# open-bldc.net
KiCad netlist of a schematic drawn in EAGLE
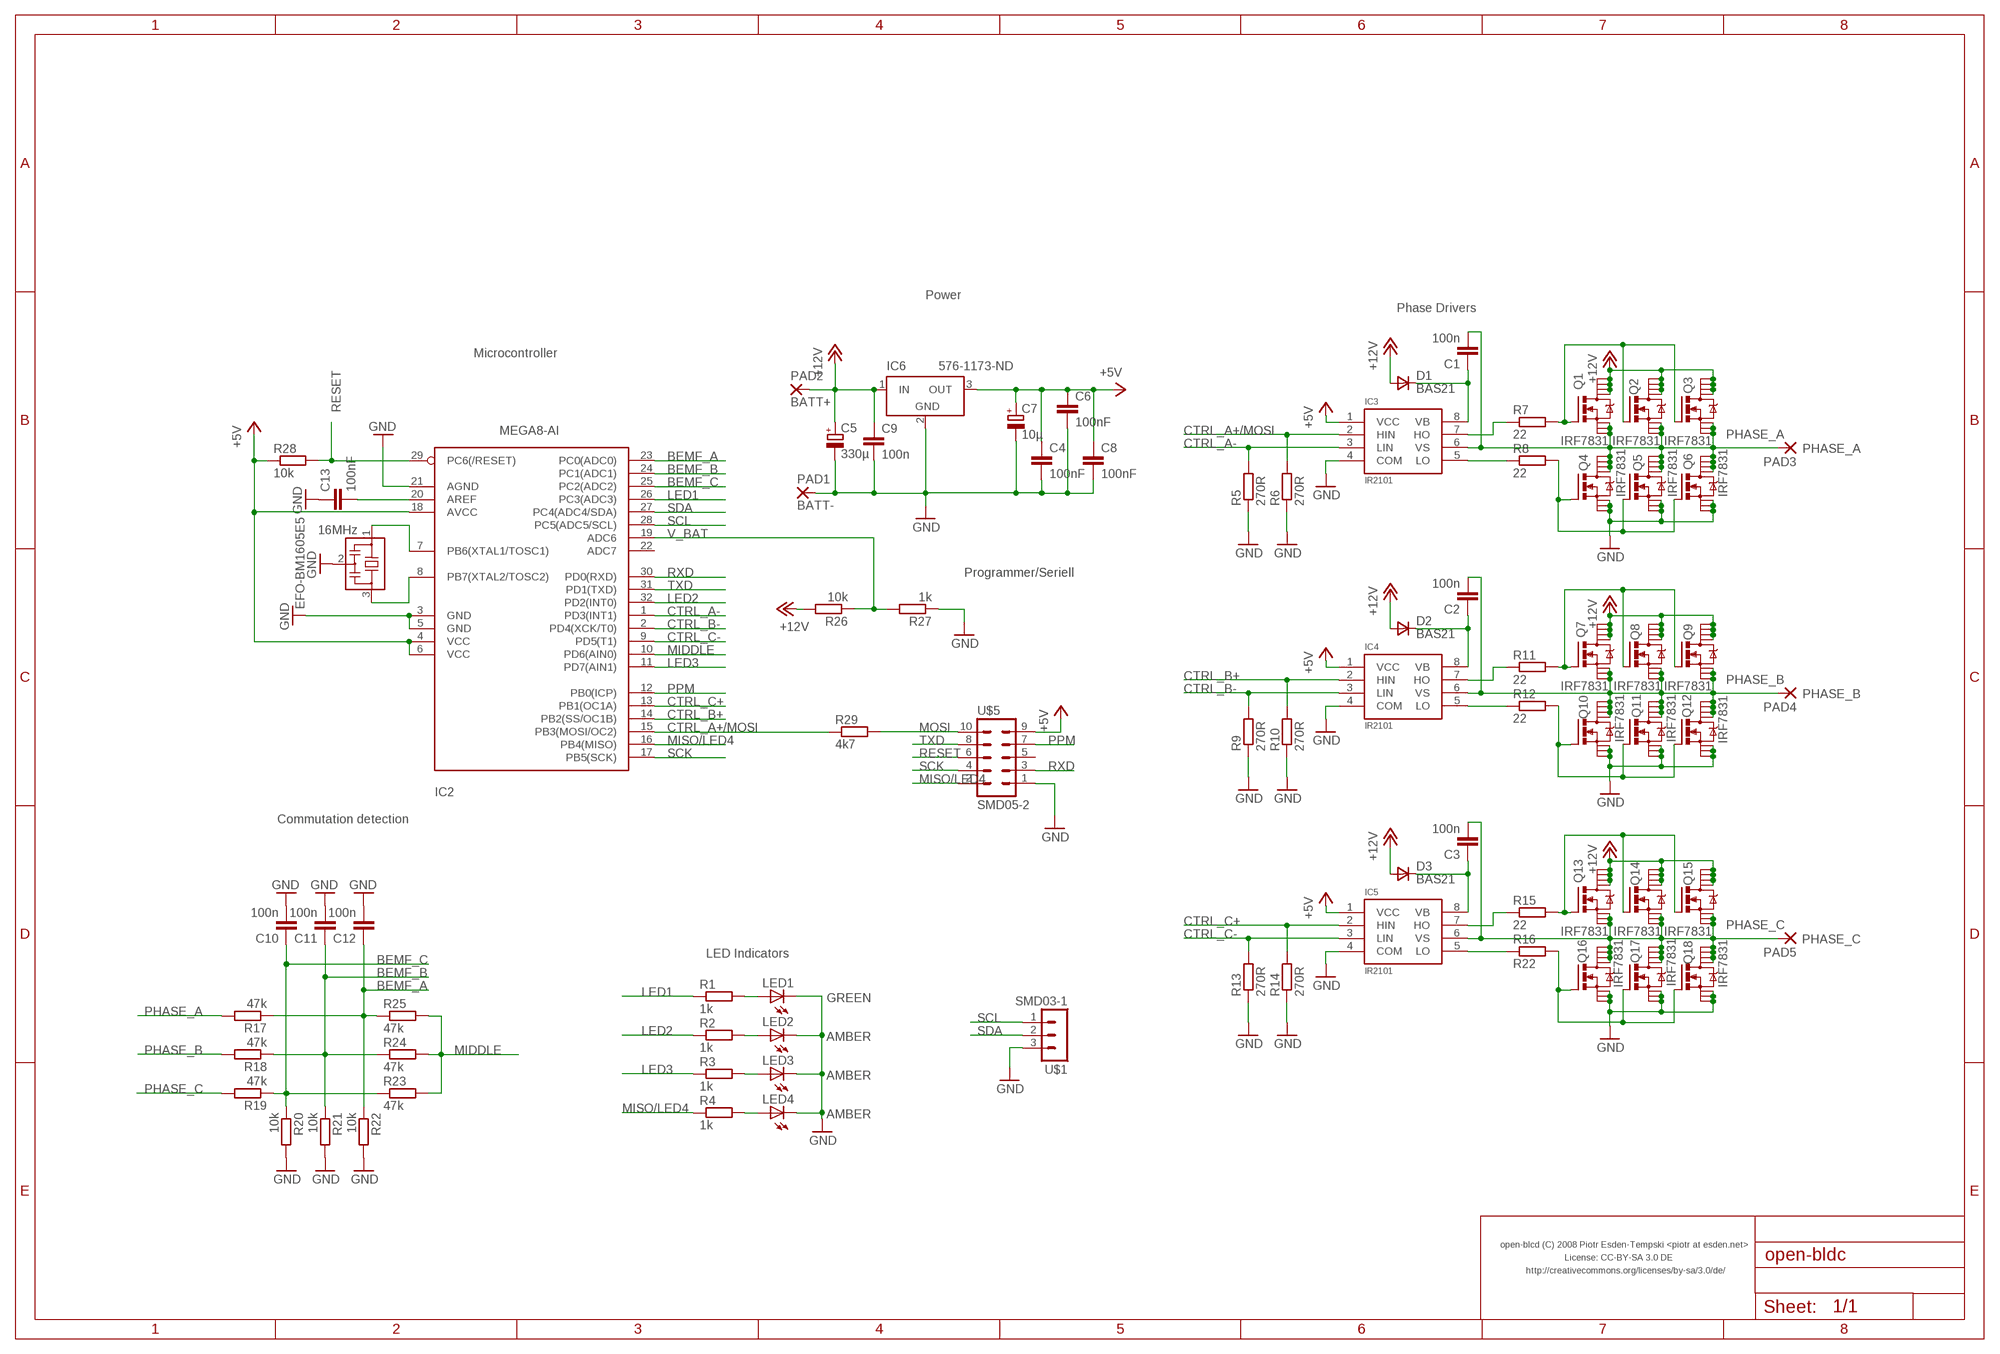
[diagram p0: schematic, sheet 1]

(export (version "E")
  (design (tool "Eeschema 10.0.6"))
  (components
    (comp (ref "C1")
      (value "100n")
      (footprint "eagle-import:C0603")
      (libsource (lib "eagle-import") (part "C-EUC0603"))
    )
    (comp (ref "C2")
      (value "100n")
      (footprint "eagle-import:C0603")
      (libsource (lib "eagle-import") (part "C-EUC0603"))
    )
    (comp (ref "C3")
      (value "100n")
      (footprint "eagle-import:C0603")
      (libsource (lib "eagle-import") (part "C-EUC0603"))
    )
    (comp (ref "C4")
      (value "100nF")
      (footprint "eagle-import:C0603")
      (libsource (lib "eagle-import") (part "C-EUC0603"))
    )
    (comp (ref "C5")
      (value "330µ")
      (footprint "eagle-import:E3,5-8")
      (libsource (lib "eagle-import") (part "CPOL-EUE3.5-8"))
    )
    (comp (ref "C6")
      (value "100nF")
      (footprint "eagle-import:C0603")
      (libsource (lib "eagle-import") (part "C-EUC0603"))
    )
    (comp (ref "C7")
      (value "10µ")
      (footprint "eagle-import:D_7343-31R")
      (libsource (lib "eagle-import") (part "CPOL-EUD/7343-31R"))
    )
    (comp (ref "C8")
      (value "100nF")
      (footprint "eagle-import:C0603")
      (libsource (lib "eagle-import") (part "C-EUC0603"))
    )
    (comp (ref "C9")
      (value "100n")
      (footprint "eagle-import:C0603")
      (libsource (lib "eagle-import") (part "C-EUC0603"))
    )
    (comp (ref "C10")
      (value "100n")
      (footprint "eagle-import:C0603")
      (libsource (lib "eagle-import") (part "C-EUC0603"))
    )
    (comp (ref "C11")
      (value "100n")
      (footprint "eagle-import:C0603")
      (libsource (lib "eagle-import") (part "C-EUC0603"))
    )
    (comp (ref "C12")
      (value "100n")
      (footprint "eagle-import:C0603")
      (libsource (lib "eagle-import") (part "C-EUC0603"))
    )
    (comp (ref "C13")
      (value "100nF")
      (footprint "eagle-import:C0603")
      (libsource (lib "eagle-import") (part "C-EUC0603"))
    )
    (comp (ref "D1")
      (value "BAS21")
      (footprint "eagle-import:SOT-23")
      (libsource (lib "eagle-import") (part "VAR2SOT23"))
    )
    (comp (ref "D2")
      (value "BAS21")
      (footprint "eagle-import:SOT-23")
      (libsource (lib "eagle-import") (part "VAR2SOT23"))
    )
    (comp (ref "D3")
      (value "BAS21")
      (footprint "eagle-import:SOT-23")
      (libsource (lib "eagle-import") (part "VAR2SOT23"))
    )
    (comp (ref "EFO-BM1605E5")
      (value "16MHz")
      (footprint "eagle-import:EFOBM")
      (libsource (lib "eagle-import") (part "EFOBM"))
    )
    (comp (ref "IC2")
      (value "MEGA8-AI")
      (footprint "eagle-import:TQFP32-08")
      (libsource (lib "eagle-import") (part "MEGA8-AI"))
    )
    (comp (ref "IC3")
      (value "IR2101")
      (footprint "eagle-import:SO-8")
      (libsource (lib "eagle-import") (part "IR2101"))
    )
    (comp (ref "IC4")
      (value "IR2101")
      (footprint "eagle-import:SO-8")
      (libsource (lib "eagle-import") (part "IR2101"))
    )
    (comp (ref "IC5")
      (value "IR2101")
      (footprint "eagle-import:SO-8")
      (libsource (lib "eagle-import") (part "IR2101"))
    )
    (comp (ref "IC6")
      (value "576-1173-ND")
      (footprint "eagle-import:SOT223")
      (libsource (lib "eagle-import") (part "LT1129CST5"))
    )
    (comp (ref "LED1")
      (value "GREEN")
      (footprint "eagle-import:CHIP-LED0603")
      (libsource (lib "eagle-import") (part "LEDCHIP-LED0603"))
    )
    (comp (ref "LED2")
      (value "AMBER")
      (footprint "eagle-import:CHIP-LED0603")
      (libsource (lib "eagle-import") (part "LEDCHIP-LED0603"))
    )
    (comp (ref "LED3")
      (value "AMBER")
      (footprint "eagle-import:CHIP-LED0603")
      (libsource (lib "eagle-import") (part "LEDCHIP-LED0603"))
    )
    (comp (ref "LED4")
      (value "AMBER")
      (footprint "eagle-import:CHIP-LED0603")
      (libsource (lib "eagle-import") (part "LEDCHIP-LED0603"))
    )
    (comp (ref "PAD1")
      (value "BATT-")
      (footprint "eagle-import:SMD2,54-5,08")
      (libsource (lib "eagle-import") (part "SMD5"))
    )
    (comp (ref "PAD2")
      (value "BATT+")
      (footprint "eagle-import:SMD2,54-5,08")
      (libsource (lib "eagle-import") (part "SMD5"))
    )
    (comp (ref "PAD3")
      (value "PHASE_A")
      (footprint "eagle-import:SMD2,54-5,08")
      (libsource (lib "eagle-import") (part "SMD5"))
    )
    (comp (ref "PAD4")
      (value "PHASE_B")
      (footprint "eagle-import:SMD2,54-5,08")
      (libsource (lib "eagle-import") (part "SMD5"))
    )
    (comp (ref "PAD5")
      (value "PHASE_C")
      (footprint "eagle-import:SMD2,54-5,08")
      (libsource (lib "eagle-import") (part "SMD5"))
    )
    (comp (ref "Q1")
      (value "IRF7831")
      (footprint "eagle-import:SO-08")
      (libsource (lib "eagle-import") (part "N-MOSFET-SO8S"))
    )
    (comp (ref "Q2")
      (value "IRF7831")
      (footprint "eagle-import:SO-08")
      (libsource (lib "eagle-import") (part "N-MOSFET-SO8S"))
    )
    (comp (ref "Q3")
      (value "IRF7831")
      (footprint "eagle-import:SO-08")
      (libsource (lib "eagle-import") (part "N-MOSFET-SO8S"))
    )
    (comp (ref "Q4")
      (value "IRF7831")
      (footprint "eagle-import:SO-08")
      (libsource (lib "eagle-import") (part "N-MOSFET-SO8S"))
    )
    (comp (ref "Q5")
      (value "IRF7831")
      (footprint "eagle-import:SO-08")
      (libsource (lib "eagle-import") (part "N-MOSFET-SO8S"))
    )
    (comp (ref "Q6")
      (value "IRF7831")
      (footprint "eagle-import:SO-08")
      (libsource (lib "eagle-import") (part "N-MOSFET-SO8S"))
    )
    (comp (ref "Q7")
      (value "IRF7831")
      (footprint "eagle-import:SO-08")
      (libsource (lib "eagle-import") (part "N-MOSFET-SO8S"))
    )
    (comp (ref "Q8")
      (value "IRF7831")
      (footprint "eagle-import:SO-08")
      (libsource (lib "eagle-import") (part "N-MOSFET-SO8S"))
    )
    (comp (ref "Q9")
      (value "IRF7831")
      (footprint "eagle-import:SO-08")
      (libsource (lib "eagle-import") (part "N-MOSFET-SO8S"))
    )
    (comp (ref "Q10")
      (value "IRF7831")
      (footprint "eagle-import:SO-08")
      (libsource (lib "eagle-import") (part "N-MOSFET-SO8S"))
    )
    (comp (ref "Q11")
      (value "IRF7831")
      (footprint "eagle-import:SO-08")
      (libsource (lib "eagle-import") (part "N-MOSFET-SO8S"))
    )
    (comp (ref "Q12")
      (value "IRF7831")
      (footprint "eagle-import:SO-08")
      (libsource (lib "eagle-import") (part "N-MOSFET-SO8S"))
    )
    (comp (ref "Q13")
      (value "IRF7831")
      (footprint "eagle-import:SO-08")
      (libsource (lib "eagle-import") (part "N-MOSFET-SO8S"))
    )
    (comp (ref "Q14")
      (value "IRF7831")
      (footprint "eagle-import:SO-08")
      (libsource (lib "eagle-import") (part "N-MOSFET-SO8S"))
    )
    (comp (ref "Q15")
      (value "IRF7831")
      (footprint "eagle-import:SO-08")
      (libsource (lib "eagle-import") (part "N-MOSFET-SO8S"))
    )
    (comp (ref "Q16")
      (value "IRF7831")
      (footprint "eagle-import:SO-08")
      (libsource (lib "eagle-import") (part "N-MOSFET-SO8S"))
    )
    (comp (ref "Q17")
      (value "IRF7831")
      (footprint "eagle-import:SO-08")
      (libsource (lib "eagle-import") (part "N-MOSFET-SO8S"))
    )
    (comp (ref "Q18")
      (value "IRF7831")
      (footprint "eagle-import:SO-08")
      (libsource (lib "eagle-import") (part "N-MOSFET-SO8S"))
    )
    (comp (ref "R1")
      (value "1k")
      (footprint "eagle-import:R0603")
      (libsource (lib "eagle-import") (part "R-EU_R0603"))
    )
    (comp (ref "R2")
      (value "1k")
      (footprint "eagle-import:R0603")
      (libsource (lib "eagle-import") (part "R-EU_R0603"))
    )
    (comp (ref "R3")
      (value "1k")
      (footprint "eagle-import:R0603")
      (libsource (lib "eagle-import") (part "R-EU_R0603"))
    )
    (comp (ref "R4")
      (value "1k")
      (footprint "eagle-import:R0603")
      (libsource (lib "eagle-import") (part "R-EU_R0603"))
    )
    (comp (ref "R5")
      (value "270R")
      (footprint "eagle-import:R0603")
      (libsource (lib "eagle-import") (part "R-EU_R0603"))
    )
    (comp (ref "R6")
      (value "270R")
      (footprint "eagle-import:R0603")
      (libsource (lib "eagle-import") (part "R-EU_R0603"))
    )
    (comp (ref "R7")
      (value "22")
      (footprint "eagle-import:R0603")
      (libsource (lib "eagle-import") (part "R-EU_R0603"))
    )
    (comp (ref "R8")
      (value "22")
      (footprint "eagle-import:R0603")
      (libsource (lib "eagle-import") (part "R-EU_R0603"))
    )
    (comp (ref "R9")
      (value "270R")
      (footprint "eagle-import:R0603")
      (libsource (lib "eagle-import") (part "R-EU_R0603"))
    )
    (comp (ref "R10")
      (value "270R")
      (footprint "eagle-import:R0603")
      (libsource (lib "eagle-import") (part "R-EU_R0603"))
    )
    (comp (ref "R11")
      (value "22")
      (footprint "eagle-import:R0603")
      (libsource (lib "eagle-import") (part "R-EU_R0603"))
    )
    (comp (ref "R12")
      (value "22")
      (footprint "eagle-import:R0603")
      (libsource (lib "eagle-import") (part "R-EU_R0603"))
    )
    (comp (ref "R13")
      (value "270R")
      (footprint "eagle-import:R0603")
      (libsource (lib "eagle-import") (part "R-EU_R0603"))
    )
    (comp (ref "R14")
      (value "270R")
      (footprint "eagle-import:R0603")
      (libsource (lib "eagle-import") (part "R-EU_R0603"))
    )
    (comp (ref "R15")
      (value "22")
      (footprint "eagle-import:R0603")
      (libsource (lib "eagle-import") (part "R-EU_R0603"))
    )
    (comp (ref "R16")
      (value "R22")
      (footprint "eagle-import:R0603")
      (libsource (lib "eagle-import") (part "R-EU_R0603"))
    )
    (comp (ref "R17")
      (value "47k")
      (footprint "eagle-import:R0603")
      (libsource (lib "eagle-import") (part "R-EU_R0603"))
    )
    (comp (ref "R18")
      (value "47k")
      (footprint "eagle-import:R0603")
      (libsource (lib "eagle-import") (part "R-EU_R0603"))
    )
    (comp (ref "R19")
      (value "47k")
      (footprint "eagle-import:R0603")
      (libsource (lib "eagle-import") (part "R-EU_R0603"))
    )
    (comp (ref "R20")
      (value "10k")
      (footprint "eagle-import:R0603")
      (libsource (lib "eagle-import") (part "R-EU_R0603"))
    )
    (comp (ref "R21")
      (value "10k")
      (footprint "eagle-import:R0603")
      (libsource (lib "eagle-import") (part "R-EU_R0603"))
    )
    (comp (ref "R22")
      (value "10k")
      (footprint "eagle-import:R0603")
      (libsource (lib "eagle-import") (part "R-EU_R0603"))
    )
    (comp (ref "R23")
      (value "47k")
      (footprint "eagle-import:R0603")
      (libsource (lib "eagle-import") (part "R-EU_R0603"))
    )
    (comp (ref "R24")
      (value "47k")
      (footprint "eagle-import:R0603")
      (libsource (lib "eagle-import") (part "R-EU_R0603"))
    )
    (comp (ref "R25")
      (value "47k")
      (footprint "eagle-import:R0603")
      (libsource (lib "eagle-import") (part "R-EU_R0603"))
    )
    (comp (ref "R26")
      (value "10k")
      (footprint "eagle-import:R0603")
      (libsource (lib "eagle-import") (part "R-EU_R0603"))
    )
    (comp (ref "R27")
      (value "1k")
      (footprint "eagle-import:R0603")
      (libsource (lib "eagle-import") (part "R-EU_R0603"))
    )
    (comp (ref "R28")
      (value "10k")
      (footprint "eagle-import:R0603")
      (libsource (lib "eagle-import") (part "R-EU_R0603"))
    )
    (comp (ref "R29")
      (value "4k7")
      (footprint "eagle-import:R0603")
      (libsource (lib "eagle-import") (part "R-EU_R0603"))
    )
    (comp (ref "U$1")
      (value "SMD03-1")
      (footprint "eagle-import:SMD03-1")
      (libsource (lib "eagle-import") (part "SMD03-1"))
    )
    (comp (ref "U$5")
      (value "SMD05-2")
      (footprint "eagle-import:SMD05-2")
      (libsource (lib "eagle-import") (part "SMD05-2"))
    )
  )
  (nets
    (net (code "1") (name "+5V") (class "Default")
      (node (ref "C4") (pin "1") (pinfunction "1_1") (pintype "passive"))
      (node (ref "C6") (pin "1") (pinfunction "1_1") (pintype "passive"))
      (node (ref "C7") (pin "+") (pinfunction "+_+") (pintype "passive"))
      (node (ref "C8") (pin "1") (pinfunction "1_1") (pintype "passive"))
      (node (ref "IC2") (pin "18") (pinfunction "AVCC_18") (pintype "power_in"))
      (node (ref "IC2") (pin "4") (pinfunction "VCC_4") (pintype "power_in"))
      (node (ref "IC2") (pin "6") (pinfunction "VCC_6") (pintype "power_in"))
      (node (ref "IC3") (pin "1") (pinfunction "VCC_1") (pintype "bidirectional"))
      (node (ref "IC4") (pin "1") (pinfunction "VCC_1") (pintype "bidirectional"))
      (node (ref "IC5") (pin "1") (pinfunction "VCC_1") (pintype "bidirectional"))
      (node (ref "IC6") (pin "3") (pinfunction "OUT_3") (pintype "output"))
      (node (ref "R28") (pin "1") (pinfunction "1_1") (pintype "passive"))
      (node (ref "U$5") (pin "9") (pinfunction "9_9") (pintype "passive"))
    )
    (net (code "2") (name "+12V") (class "Default")
      (node (ref "C5") (pin "+") (pinfunction "+_+") (pintype "passive"))
      (node (ref "C9") (pin "1") (pinfunction "1_1") (pintype "passive"))
      (node (ref "D1") (pin "3") (pinfunction "A_3") (pintype "passive"))
      (node (ref "D2") (pin "3") (pinfunction "A_3") (pintype "passive"))
      (node (ref "D3") (pin "3") (pinfunction "A_3") (pintype "passive"))
      (node (ref "IC6") (pin "1") (pinfunction "IN_1") (pintype "input"))
      (node (ref "PAD2") (pin "1") (pinfunction "P_1") (pintype "passive"))
      (node (ref "Q1") (pin "5") (pinfunction "D_5") (pintype "passive"))
      (node (ref "Q1") (pin "6") (pinfunction "D_6") (pintype "passive"))
      (node (ref "Q1") (pin "7") (pinfunction "D_7") (pintype "passive"))
      (node (ref "Q1") (pin "8") (pinfunction "D_8") (pintype "passive"))
      (node (ref "Q13") (pin "5") (pinfunction "D_5") (pintype "passive"))
      (node (ref "Q13") (pin "6") (pinfunction "D_6") (pintype "passive"))
      (node (ref "Q13") (pin "7") (pinfunction "D_7") (pintype "passive"))
      (node (ref "Q13") (pin "8") (pinfunction "D_8") (pintype "passive"))
      (node (ref "Q14") (pin "5") (pinfunction "D_5") (pintype "passive"))
      (node (ref "Q14") (pin "6") (pinfunction "D_6") (pintype "passive"))
      (node (ref "Q14") (pin "7") (pinfunction "D_7") (pintype "passive"))
      (node (ref "Q14") (pin "8") (pinfunction "D_8") (pintype "passive"))
      (node (ref "Q15") (pin "5") (pinfunction "D_5") (pintype "passive"))
      (node (ref "Q15") (pin "6") (pinfunction "D_6") (pintype "passive"))
      (node (ref "Q15") (pin "7") (pinfunction "D_7") (pintype "passive"))
      (node (ref "Q15") (pin "8") (pinfunction "D_8") (pintype "passive"))
      (node (ref "Q2") (pin "5") (pinfunction "D_5") (pintype "passive"))
      (node (ref "Q2") (pin "6") (pinfunction "D_6") (pintype "passive"))
      (node (ref "Q2") (pin "7") (pinfunction "D_7") (pintype "passive"))
      (node (ref "Q2") (pin "8") (pinfunction "D_8") (pintype "passive"))
      (node (ref "Q3") (pin "5") (pinfunction "D_5") (pintype "passive"))
      (node (ref "Q3") (pin "6") (pinfunction "D_6") (pintype "passive"))
      (node (ref "Q3") (pin "7") (pinfunction "D_7") (pintype "passive"))
      (node (ref "Q3") (pin "8") (pinfunction "D_8") (pintype "passive"))
      (node (ref "Q7") (pin "5") (pinfunction "D_5") (pintype "passive"))
      (node (ref "Q7") (pin "6") (pinfunction "D_6") (pintype "passive"))
      (node (ref "Q7") (pin "7") (pinfunction "D_7") (pintype "passive"))
      (node (ref "Q7") (pin "8") (pinfunction "D_8") (pintype "passive"))
      (node (ref "Q8") (pin "5") (pinfunction "D_5") (pintype "passive"))
      (node (ref "Q8") (pin "6") (pinfunction "D_6") (pintype "passive"))
      (node (ref "Q8") (pin "7") (pinfunction "D_7") (pintype "passive"))
      (node (ref "Q8") (pin "8") (pinfunction "D_8") (pintype "passive"))
      (node (ref "Q9") (pin "5") (pinfunction "D_5") (pintype "passive"))
      (node (ref "Q9") (pin "6") (pinfunction "D_6") (pintype "passive"))
      (node (ref "Q9") (pin "7") (pinfunction "D_7") (pintype "passive"))
      (node (ref "Q9") (pin "8") (pinfunction "D_8") (pintype "passive"))
      (node (ref "R26") (pin "2") (pinfunction "2_2") (pintype "passive"))
    )
    (net (code "3") (name "/BEMF_A") (class "Default")
      (node (ref "C12") (pin "1") (pinfunction "1_1") (pintype "passive"))
      (node (ref "IC2") (pin "23") (pinfunction "PC0(ADC0)_23") (pintype "bidirectional"))
      (node (ref "R17") (pin "1") (pinfunction "1_1") (pintype "passive"))
      (node (ref "R22") (pin "1") (pinfunction "1_1") (pintype "passive"))
      (node (ref "R25") (pin "1") (pinfunction "1_1") (pintype "passive"))
    )
    (net (code "4") (name "/BEMF_B") (class "Default")
      (node (ref "C11") (pin "1") (pinfunction "1_1") (pintype "passive"))
      (node (ref "IC2") (pin "24") (pinfunction "PC1(ADC1)_24") (pintype "bidirectional"))
      (node (ref "R18") (pin "1") (pinfunction "1_1") (pintype "passive"))
      (node (ref "R21") (pin "1") (pinfunction "1_1") (pintype "passive"))
      (node (ref "R24") (pin "1") (pinfunction "1_1") (pintype "passive"))
    )
    (net (code "5") (name "/BEMF_C") (class "Default")
      (node (ref "C10") (pin "1") (pinfunction "1_1") (pintype "passive"))
      (node (ref "IC2") (pin "25") (pinfunction "PC2(ADC2)_25") (pintype "bidirectional"))
      (node (ref "R19") (pin "1") (pinfunction "1_1") (pintype "passive"))
      (node (ref "R20") (pin "1") (pinfunction "1_1") (pintype "passive"))
      (node (ref "R23") (pin "1") (pinfunction "1_1") (pintype "passive"))
    )
    (net (code "6") (name "/CTRL_A+{slash}MOSI") (class "Default")
      (node (ref "IC2") (pin "15") (pinfunction "PB3(MOSI/OC2)_15") (pintype "bidirectional"))
      (node (ref "IC3") (pin "2") (pinfunction "HIN_2") (pintype "bidirectional"))
      (node (ref "R29") (pin "1") (pinfunction "1_1") (pintype "passive"))
      (node (ref "R6") (pin "2") (pinfunction "2_2") (pintype "passive"))
    )
    (net (code "7") (name "/CTRL_A-") (class "Default")
      (node (ref "IC2") (pin "1") (pinfunction "PD3(INT1)_1") (pintype "bidirectional"))
      (node (ref "IC3") (pin "3") (pinfunction "LIN_3") (pintype "bidirectional"))
      (node (ref "R5") (pin "2") (pinfunction "2_2") (pintype "passive"))
    )
    (net (code "8") (name "/CTRL_B+") (class "Default")
      (node (ref "IC2") (pin "14") (pinfunction "PB2(SS/OC1B)_14") (pintype "bidirectional"))
      (node (ref "IC4") (pin "2") (pinfunction "HIN_2") (pintype "bidirectional"))
      (node (ref "R10") (pin "2") (pinfunction "2_2") (pintype "passive"))
    )
    (net (code "9") (name "/CTRL_B-") (class "Default")
      (node (ref "IC2") (pin "2") (pinfunction "PD4(XCK/T0)_2") (pintype "bidirectional"))
      (node (ref "IC4") (pin "3") (pinfunction "LIN_3") (pintype "bidirectional"))
      (node (ref "R9") (pin "2") (pinfunction "2_2") (pintype "passive"))
    )
    (net (code "10") (name "/CTRL_C+") (class "Default")
      (node (ref "IC2") (pin "13") (pinfunction "PB1(OC1A)_13") (pintype "bidirectional"))
      (node (ref "IC5") (pin "2") (pinfunction "HIN_2") (pintype "bidirectional"))
      (node (ref "R14") (pin "2") (pinfunction "2_2") (pintype "passive"))
    )
    (net (code "11") (name "/CTRL_C-") (class "Default")
      (node (ref "IC2") (pin "9") (pinfunction "PD5(T1)_9") (pintype "bidirectional"))
      (node (ref "IC5") (pin "3") (pinfunction "LIN_3") (pintype "bidirectional"))
      (node (ref "R13") (pin "2") (pinfunction "2_2") (pintype "passive"))
    )
    (net (code "12") (name "/LED1") (class "Default")
      (node (ref "IC2") (pin "26") (pinfunction "PC3(ADC3)_26") (pintype "bidirectional"))
      (node (ref "R1") (pin "1") (pinfunction "1_1") (pintype "passive"))
    )
    (net (code "13") (name "/LED2") (class "Default")
      (node (ref "IC2") (pin "32") (pinfunction "PD2(INT0)_32") (pintype "bidirectional"))
      (node (ref "R2") (pin "1") (pinfunction "1_1") (pintype "passive"))
    )
    (net (code "14") (name "/LED3") (class "Default")
      (node (ref "IC2") (pin "11") (pinfunction "PD7(AIN1)_11") (pintype "bidirectional"))
      (node (ref "R3") (pin "1") (pinfunction "1_1") (pintype "passive"))
    )
    (net (code "15") (name "/MIDDLE") (class "Default")
      (node (ref "IC2") (pin "10") (pinfunction "PD6(AIN0)_10") (pintype "bidirectional"))
      (node (ref "R23") (pin "2") (pinfunction "2_2") (pintype "passive"))
      (node (ref "R24") (pin "2") (pinfunction "2_2") (pintype "passive"))
      (node (ref "R25") (pin "2") (pinfunction "2_2") (pintype "passive"))
    )
    (net (code "16") (name "/MISO{slash}LED4") (class "Default")
      (node (ref "IC2") (pin "16") (pinfunction "PB4(MISO)_16") (pintype "bidirectional"))
      (node (ref "R4") (pin "1") (pinfunction "1_1") (pintype "passive"))
      (node (ref "U$5") (pin "2") (pinfunction "2_2") (pintype "passive"))
    )
    (net (code "17") (name "/MOSI") (class "Default")
      (node (ref "R29") (pin "2") (pinfunction "2_2") (pintype "passive"))
      (node (ref "U$5") (pin "10") (pinfunction "10_10") (pintype "passive"))
    )
    (net (code "18") (name "/PHASE_A") (class "Default")
      (node (ref "C1") (pin "2") (pinfunction "2_2") (pintype "passive"))
      (node (ref "IC3") (pin "6") (pinfunction "VS_6") (pintype "bidirectional"))
      (node (ref "PAD3") (pin "1") (pinfunction "P_1") (pintype "passive"))
      (node (ref "Q1") (pin "1") (pinfunction "S_1") (pintype "passive"))
      (node (ref "Q1") (pin "2") (pinfunction "S_2") (pintype "passive"))
      (node (ref "Q1") (pin "3") (pinfunction "S_3") (pintype "passive"))
      (node (ref "Q2") (pin "1") (pinfunction "S_1") (pintype "passive"))
      (node (ref "Q2") (pin "2") (pinfunction "S_2") (pintype "passive"))
      (node (ref "Q2") (pin "3") (pinfunction "S_3") (pintype "passive"))
      (node (ref "Q3") (pin "1") (pinfunction "S_1") (pintype "passive"))
      (node (ref "Q3") (pin "2") (pinfunction "S_2") (pintype "passive"))
      (node (ref "Q3") (pin "3") (pinfunction "S_3") (pintype "passive"))
      (node (ref "Q4") (pin "5") (pinfunction "D_5") (pintype "passive"))
      (node (ref "Q4") (pin "6") (pinfunction "D_6") (pintype "passive"))
      (node (ref "Q4") (pin "7") (pinfunction "D_7") (pintype "passive"))
      (node (ref "Q4") (pin "8") (pinfunction "D_8") (pintype "passive"))
      (node (ref "Q5") (pin "5") (pinfunction "D_5") (pintype "passive"))
      (node (ref "Q5") (pin "6") (pinfunction "D_6") (pintype "passive"))
      (node (ref "Q5") (pin "7") (pinfunction "D_7") (pintype "passive"))
      (node (ref "Q5") (pin "8") (pinfunction "D_8") (pintype "passive"))
      (node (ref "Q6") (pin "5") (pinfunction "D_5") (pintype "passive"))
      (node (ref "Q6") (pin "6") (pinfunction "D_6") (pintype "passive"))
      (node (ref "Q6") (pin "7") (pinfunction "D_7") (pintype "passive"))
      (node (ref "Q6") (pin "8") (pinfunction "D_8") (pintype "passive"))
      (node (ref "R17") (pin "2") (pinfunction "2_2") (pintype "passive"))
    )
    (net (code "19") (name "/PHASE_B") (class "Default")
      (node (ref "C2") (pin "2") (pinfunction "2_2") (pintype "passive"))
      (node (ref "IC4") (pin "6") (pinfunction "VS_6") (pintype "bidirectional"))
      (node (ref "PAD4") (pin "1") (pinfunction "P_1") (pintype "passive"))
      (node (ref "Q10") (pin "5") (pinfunction "D_5") (pintype "passive"))
      (node (ref "Q10") (pin "6") (pinfunction "D_6") (pintype "passive"))
      (node (ref "Q10") (pin "7") (pinfunction "D_7") (pintype "passive"))
      (node (ref "Q10") (pin "8") (pinfunction "D_8") (pintype "passive"))
      (node (ref "Q11") (pin "5") (pinfunction "D_5") (pintype "passive"))
      (node (ref "Q11") (pin "6") (pinfunction "D_6") (pintype "passive"))
      (node (ref "Q11") (pin "7") (pinfunction "D_7") (pintype "passive"))
      (node (ref "Q11") (pin "8") (pinfunction "D_8") (pintype "passive"))
      (node (ref "Q12") (pin "5") (pinfunction "D_5") (pintype "passive"))
      (node (ref "Q12") (pin "6") (pinfunction "D_6") (pintype "passive"))
      (node (ref "Q12") (pin "7") (pinfunction "D_7") (pintype "passive"))
      (node (ref "Q12") (pin "8") (pinfunction "D_8") (pintype "passive"))
      (node (ref "Q7") (pin "1") (pinfunction "S_1") (pintype "passive"))
      (node (ref "Q7") (pin "2") (pinfunction "S_2") (pintype "passive"))
      (node (ref "Q7") (pin "3") (pinfunction "S_3") (pintype "passive"))
      (node (ref "Q8") (pin "1") (pinfunction "S_1") (pintype "passive"))
      (node (ref "Q8") (pin "2") (pinfunction "S_2") (pintype "passive"))
      (node (ref "Q8") (pin "3") (pinfunction "S_3") (pintype "passive"))
      (node (ref "Q9") (pin "1") (pinfunction "S_1") (pintype "passive"))
      (node (ref "Q9") (pin "2") (pinfunction "S_2") (pintype "passive"))
      (node (ref "Q9") (pin "3") (pinfunction "S_3") (pintype "passive"))
      (node (ref "R18") (pin "2") (pinfunction "2_2") (pintype "passive"))
    )
    (net (code "20") (name "/PHASE_C") (class "Default")
      (node (ref "C3") (pin "2") (pinfunction "2_2") (pintype "passive"))
      (node (ref "IC5") (pin "6") (pinfunction "VS_6") (pintype "bidirectional"))
      (node (ref "PAD5") (pin "1") (pinfunction "P_1") (pintype "passive"))
      (node (ref "Q13") (pin "1") (pinfunction "S_1") (pintype "passive"))
      (node (ref "Q13") (pin "2") (pinfunction "S_2") (pintype "passive"))
      (node (ref "Q13") (pin "3") (pinfunction "S_3") (pintype "passive"))
      (node (ref "Q14") (pin "1") (pinfunction "S_1") (pintype "passive"))
      (node (ref "Q14") (pin "2") (pinfunction "S_2") (pintype "passive"))
      (node (ref "Q14") (pin "3") (pinfunction "S_3") (pintype "passive"))
      (node (ref "Q15") (pin "1") (pinfunction "S_1") (pintype "passive"))
      (node (ref "Q15") (pin "2") (pinfunction "S_2") (pintype "passive"))
      (node (ref "Q15") (pin "3") (pinfunction "S_3") (pintype "passive"))
      (node (ref "Q16") (pin "5") (pinfunction "D_5") (pintype "passive"))
      (node (ref "Q16") (pin "6") (pinfunction "D_6") (pintype "passive"))
      (node (ref "Q16") (pin "7") (pinfunction "D_7") (pintype "passive"))
      (node (ref "Q16") (pin "8") (pinfunction "D_8") (pintype "passive"))
      (node (ref "Q17") (pin "5") (pinfunction "D_5") (pintype "passive"))
      (node (ref "Q17") (pin "6") (pinfunction "D_6") (pintype "passive"))
      (node (ref "Q17") (pin "7") (pinfunction "D_7") (pintype "passive"))
      (node (ref "Q17") (pin "8") (pinfunction "D_8") (pintype "passive"))
      (node (ref "Q18") (pin "5") (pinfunction "D_5") (pintype "passive"))
      (node (ref "Q18") (pin "6") (pinfunction "D_6") (pintype "passive"))
      (node (ref "Q18") (pin "7") (pinfunction "D_7") (pintype "passive"))
      (node (ref "Q18") (pin "8") (pinfunction "D_8") (pintype "passive"))
      (node (ref "R19") (pin "2") (pinfunction "2_2") (pintype "passive"))
    )
    (net (code "21") (name "/PPM") (class "Default")
      (node (ref "IC2") (pin "12") (pinfunction "PB0(ICP)_12") (pintype "bidirectional"))
      (node (ref "U$5") (pin "7") (pinfunction "7_7") (pintype "passive"))
    )
    (net (code "22") (name "/RESET") (class "Default")
      (node (ref "IC2") (pin "29") (pinfunction "PC6(/RESET)_29") (pintype "bidirectional"))
      (node (ref "R28") (pin "2") (pinfunction "2_2") (pintype "passive"))
      (node (ref "U$5") (pin "6") (pinfunction "6_6") (pintype "passive"))
    )
    (net (code "23") (name "/RXD") (class "Default")
      (node (ref "IC2") (pin "30") (pinfunction "PD0(RXD)_30") (pintype "bidirectional"))
      (node (ref "U$5") (pin "3") (pinfunction "3_3") (pintype "passive"))
    )
    (net (code "24") (name "/SCK") (class "Default")
      (node (ref "IC2") (pin "17") (pinfunction "PB5(SCK)_17") (pintype "bidirectional"))
      (node (ref "U$5") (pin "4") (pinfunction "4_4") (pintype "passive"))
    )
    (net (code "25") (name "/SCL") (class "Default")
      (node (ref "IC2") (pin "28") (pinfunction "PC5(ADC5/SCL)_28") (pintype "bidirectional"))
      (node (ref "U$1") (pin "1") (pinfunction "1_1") (pintype "passive"))
    )
    (net (code "26") (name "/SDA") (class "Default")
      (node (ref "IC2") (pin "27") (pinfunction "PC4(ADC4/SDA)_27") (pintype "bidirectional"))
      (node (ref "U$1") (pin "2") (pinfunction "2_2") (pintype "passive"))
    )
    (net (code "27") (name "/TXD") (class "Default")
      (node (ref "IC2") (pin "31") (pinfunction "PD1(TXD)_31") (pintype "bidirectional"))
      (node (ref "U$5") (pin "8") (pinfunction "8_8") (pintype "passive"))
    )
    (net (code "28") (name "/V_BAT") (class "Default")
      (node (ref "IC2") (pin "19") (pinfunction "ADC6_19") (pintype "bidirectional"))
      (node (ref "R26") (pin "1") (pinfunction "1_1") (pintype "passive"))
      (node (ref "R27") (pin "2") (pinfunction "2_2") (pintype "passive"))
    )
    (net (code "29") (name "GND") (class "Default")
      (node (ref "C10") (pin "2") (pinfunction "2_2") (pintype "passive"))
      (node (ref "C11") (pin "2") (pinfunction "2_2") (pintype "passive"))
      (node (ref "C12") (pin "2") (pinfunction "2_2") (pintype "passive"))
      (node (ref "C13") (pin "1") (pinfunction "1_1") (pintype "passive"))
      (node (ref "C4") (pin "2") (pinfunction "2_2") (pintype "passive"))
      (node (ref "C5") (pin "-") (pinfunction "-_-") (pintype "passive"))
      (node (ref "C6") (pin "2") (pinfunction "2_2") (pintype "passive"))
      (node (ref "C7") (pin "-") (pinfunction "-_-") (pintype "passive"))
      (node (ref "C8") (pin "2") (pinfunction "2_2") (pintype "passive"))
      (node (ref "C9") (pin "2") (pinfunction "2_2") (pintype "passive"))
      (node (ref "EFO-BM1605E5") (pin "2") (pinfunction "2_2") (pintype "passive"))
      (node (ref "IC2") (pin "21") (pinfunction "AGND_21") (pintype "power_in"))
      (node (ref "IC2") (pin "3") (pinfunction "GND_3") (pintype "power_in"))
      (node (ref "IC2") (pin "5") (pinfunction "GND_5") (pintype "power_in"))
      (node (ref "IC3") (pin "4") (pinfunction "COM_4") (pintype "bidirectional"))
      (node (ref "IC4") (pin "4") (pinfunction "COM_4") (pintype "bidirectional"))
      (node (ref "IC5") (pin "4") (pinfunction "COM_4") (pintype "bidirectional"))
      (node (ref "IC6") (pin "2") (pinfunction "GND_2") (pintype "power_in"))
      (node (ref "LED1") (pin "C") (pinfunction "C_C") (pintype "passive"))
      (node (ref "LED2") (pin "C") (pinfunction "C_C") (pintype "passive"))
      (node (ref "LED3") (pin "C") (pinfunction "C_C") (pintype "passive"))
      (node (ref "LED4") (pin "C") (pinfunction "C_C") (pintype "passive"))
      (node (ref "PAD1") (pin "1") (pinfunction "P_1") (pintype "passive"))
      (node (ref "Q10") (pin "1") (pinfunction "S_1") (pintype "passive"))
      (node (ref "Q10") (pin "2") (pinfunction "S_2") (pintype "passive"))
      (node (ref "Q10") (pin "3") (pinfunction "S_3") (pintype "passive"))
      (node (ref "Q11") (pin "1") (pinfunction "S_1") (pintype "passive"))
      (node (ref "Q11") (pin "2") (pinfunction "S_2") (pintype "passive"))
      (node (ref "Q11") (pin "3") (pinfunction "S_3") (pintype "passive"))
      (node (ref "Q12") (pin "1") (pinfunction "S_1") (pintype "passive"))
      (node (ref "Q12") (pin "2") (pinfunction "S_2") (pintype "passive"))
      (node (ref "Q12") (pin "3") (pinfunction "S_3") (pintype "passive"))
      (node (ref "Q16") (pin "1") (pinfunction "S_1") (pintype "passive"))
      (node (ref "Q16") (pin "2") (pinfunction "S_2") (pintype "passive"))
      (node (ref "Q16") (pin "3") (pinfunction "S_3") (pintype "passive"))
      (node (ref "Q17") (pin "1") (pinfunction "S_1") (pintype "passive"))
      (node (ref "Q17") (pin "2") (pinfunction "S_2") (pintype "passive"))
      (node (ref "Q17") (pin "3") (pinfunction "S_3") (pintype "passive"))
      (node (ref "Q18") (pin "1") (pinfunction "S_1") (pintype "passive"))
      (node (ref "Q18") (pin "2") (pinfunction "S_2") (pintype "passive"))
      (node (ref "Q18") (pin "3") (pinfunction "S_3") (pintype "passive"))
      (node (ref "Q4") (pin "1") (pinfunction "S_1") (pintype "passive"))
      (node (ref "Q4") (pin "2") (pinfunction "S_2") (pintype "passive"))
      (node (ref "Q4") (pin "3") (pinfunction "S_3") (pintype "passive"))
      (node (ref "Q5") (pin "1") (pinfunction "S_1") (pintype "passive"))
      (node (ref "Q5") (pin "2") (pinfunction "S_2") (pintype "passive"))
      (node (ref "Q5") (pin "3") (pinfunction "S_3") (pintype "passive"))
      (node (ref "Q6") (pin "1") (pinfunction "S_1") (pintype "passive"))
      (node (ref "Q6") (pin "2") (pinfunction "S_2") (pintype "passive"))
      (node (ref "Q6") (pin "3") (pinfunction "S_3") (pintype "passive"))
      (node (ref "R10") (pin "1") (pinfunction "1_1") (pintype "passive"))
      (node (ref "R13") (pin "1") (pinfunction "1_1") (pintype "passive"))
      (node (ref "R14") (pin "1") (pinfunction "1_1") (pintype "passive"))
      (node (ref "R20") (pin "2") (pinfunction "2_2") (pintype "passive"))
      (node (ref "R21") (pin "2") (pinfunction "2_2") (pintype "passive"))
      (node (ref "R22") (pin "2") (pinfunction "2_2") (pintype "passive"))
      (node (ref "R27") (pin "1") (pinfunction "1_1") (pintype "passive"))
      (node (ref "R5") (pin "1") (pinfunction "1_1") (pintype "passive"))
      (node (ref "R6") (pin "1") (pinfunction "1_1") (pintype "passive"))
      (node (ref "R9") (pin "1") (pinfunction "1_1") (pintype "passive"))
      (node (ref "U$1") (pin "3") (pinfunction "3_3") (pintype "passive"))
      (node (ref "U$5") (pin "1") (pinfunction "1_1") (pintype "passive"))
    )
    (net (code "30") (name "Net-(D1-C)") (class "Default")
      (node (ref "C1") (pin "1") (pinfunction "1_1") (pintype "passive"))
      (node (ref "D1") (pin "1") (pinfunction "C_1") (pintype "passive"))
      (node (ref "IC3") (pin "8") (pinfunction "VB_8") (pintype "bidirectional"))
    )
    (net (code "31") (name "Net-(D2-C)") (class "Default")
      (node (ref "C2") (pin "1") (pinfunction "1_1") (pintype "passive"))
      (node (ref "D2") (pin "1") (pinfunction "C_1") (pintype "passive"))
      (node (ref "IC4") (pin "8") (pinfunction "VB_8") (pintype "bidirectional"))
    )
    (net (code "32") (name "Net-(D3-C)") (class "Default")
      (node (ref "C3") (pin "1") (pinfunction "1_1") (pintype "passive"))
      (node (ref "D3") (pin "1") (pinfunction "C_1") (pintype "passive"))
      (node (ref "IC5") (pin "8") (pinfunction "VB_8") (pintype "bidirectional"))
    )
    (net (code "33") (name "Net-(IC2-AREF)") (class "Default")
      (node (ref "C13") (pin "2") (pinfunction "2_2") (pintype "passive"))
      (node (ref "IC2") (pin "20") (pinfunction "AREF_20") (pintype "passive"))
    )
    (net (code "34") (name "Net-(IC2-PB6(XTAL1{slash}TOSC1))") (class "Default")
      (node (ref "EFO-BM1605E5") (pin "1") (pinfunction "1_1") (pintype "passive"))
      (node (ref "IC2") (pin "7") (pinfunction "PB6(XTAL1/TOSC1)_7") (pintype "bidirectional"))
    )
    (net (code "35") (name "Net-(IC2-PB7(XTAL2{slash}TOSC2))") (class "Default")
      (node (ref "EFO-BM1605E5") (pin "3") (pinfunction "3_3") (pintype "passive"))
      (node (ref "IC2") (pin "8") (pinfunction "PB7(XTAL2/TOSC2)_8") (pintype "bidirectional"))
    )
    (net (code "36") (name "Net-(IC3-HO)") (class "Default")
      (node (ref "IC3") (pin "7") (pinfunction "HO_7") (pintype "bidirectional"))
      (node (ref "R7") (pin "1") (pinfunction "1_1") (pintype "passive"))
    )
    (net (code "37") (name "Net-(IC3-LO)") (class "Default")
      (node (ref "IC3") (pin "5") (pinfunction "LO_5") (pintype "bidirectional"))
      (node (ref "R8") (pin "1") (pinfunction "1_1") (pintype "passive"))
    )
    (net (code "38") (name "Net-(IC4-HO)") (class "Default")
      (node (ref "IC4") (pin "7") (pinfunction "HO_7") (pintype "bidirectional"))
      (node (ref "R11") (pin "1") (pinfunction "1_1") (pintype "passive"))
    )
    (net (code "39") (name "Net-(IC4-LO)") (class "Default")
      (node (ref "IC4") (pin "5") (pinfunction "LO_5") (pintype "bidirectional"))
      (node (ref "R12") (pin "1") (pinfunction "1_1") (pintype "passive"))
    )
    (net (code "40") (name "Net-(IC5-HO)") (class "Default")
      (node (ref "IC5") (pin "7") (pinfunction "HO_7") (pintype "bidirectional"))
      (node (ref "R15") (pin "1") (pinfunction "1_1") (pintype "passive"))
    )
    (net (code "41") (name "Net-(IC5-LO)") (class "Default")
      (node (ref "IC5") (pin "5") (pinfunction "LO_5") (pintype "bidirectional"))
      (node (ref "R16") (pin "1") (pinfunction "1_1") (pintype "passive"))
    )
    (net (code "42") (name "Net-(LED1-PadA)") (class "Default")
      (node (ref "LED1") (pin "A") (pinfunction "A_A") (pintype "passive"))
      (node (ref "R1") (pin "2") (pinfunction "2_2") (pintype "passive"))
    )
    (net (code "43") (name "Net-(LED2-PadA)") (class "Default")
      (node (ref "LED2") (pin "A") (pinfunction "A_A") (pintype "passive"))
      (node (ref "R2") (pin "2") (pinfunction "2_2") (pintype "passive"))
    )
    (net (code "44") (name "Net-(LED3-PadA)") (class "Default")
      (node (ref "LED3") (pin "A") (pinfunction "A_A") (pintype "passive"))
      (node (ref "R3") (pin "2") (pinfunction "2_2") (pintype "passive"))
    )
    (net (code "45") (name "Net-(LED4-PadA)") (class "Default")
      (node (ref "LED4") (pin "A") (pinfunction "A_A") (pintype "passive"))
      (node (ref "R4") (pin "2") (pinfunction "2_2") (pintype "passive"))
    )
    (net (code "46") (name "Net-(Q1-G)") (class "Default")
      (node (ref "Q1") (pin "4") (pinfunction "G_4") (pintype "passive"))
      (node (ref "Q2") (pin "4") (pinfunction "G_4") (pintype "passive"))
      (node (ref "Q3") (pin "4") (pinfunction "G_4") (pintype "passive"))
      (node (ref "R7") (pin "2") (pinfunction "2_2") (pintype "passive"))
    )
    (net (code "47") (name "Net-(Q4-G)") (class "Default")
      (node (ref "Q4") (pin "4") (pinfunction "G_4") (pintype "passive"))
      (node (ref "Q5") (pin "4") (pinfunction "G_4") (pintype "passive"))
      (node (ref "Q6") (pin "4") (pinfunction "G_4") (pintype "passive"))
      (node (ref "R8") (pin "2") (pinfunction "2_2") (pintype "passive"))
    )
    (net (code "48") (name "Net-(Q7-G)") (class "Default")
      (node (ref "Q7") (pin "4") (pinfunction "G_4") (pintype "passive"))
      (node (ref "Q8") (pin "4") (pinfunction "G_4") (pintype "passive"))
      (node (ref "Q9") (pin "4") (pinfunction "G_4") (pintype "passive"))
      (node (ref "R11") (pin "2") (pinfunction "2_2") (pintype "passive"))
    )
    (net (code "49") (name "Net-(Q10-G)") (class "Default")
      (node (ref "Q10") (pin "4") (pinfunction "G_4") (pintype "passive"))
      (node (ref "Q11") (pin "4") (pinfunction "G_4") (pintype "passive"))
      (node (ref "Q12") (pin "4") (pinfunction "G_4") (pintype "passive"))
      (node (ref "R12") (pin "2") (pinfunction "2_2") (pintype "passive"))
    )
    (net (code "50") (name "Net-(Q13-G)") (class "Default")
      (node (ref "Q13") (pin "4") (pinfunction "G_4") (pintype "passive"))
      (node (ref "Q14") (pin "4") (pinfunction "G_4") (pintype "passive"))
      (node (ref "Q15") (pin "4") (pinfunction "G_4") (pintype "passive"))
      (node (ref "R15") (pin "2") (pinfunction "2_2") (pintype "passive"))
    )
    (net (code "51") (name "Net-(Q16-G)") (class "Default")
      (node (ref "Q16") (pin "4") (pinfunction "G_4") (pintype "passive"))
      (node (ref "Q17") (pin "4") (pinfunction "G_4") (pintype "passive"))
      (node (ref "Q18") (pin "4") (pinfunction "G_4") (pintype "passive"))
      (node (ref "R16") (pin "2") (pinfunction "2_2") (pintype "passive"))
    )
    (net (code "52") (name "unconnected-(IC2-ADC7-Pad22)") (class "Default")
      (node (ref "IC2") (pin "22") (pinfunction "ADC7_22") (pintype "bidirectional"))
    )
    (net (code "53") (name "unconnected-(U$5-Pad5)") (class "Default")
      (node (ref "U$5") (pin "5") (pinfunction "5_5") (pintype "passive"))
    )
  )
)
